# AIR_Connection.net
KiCad netlist of a schematic drawn in Altium Designer
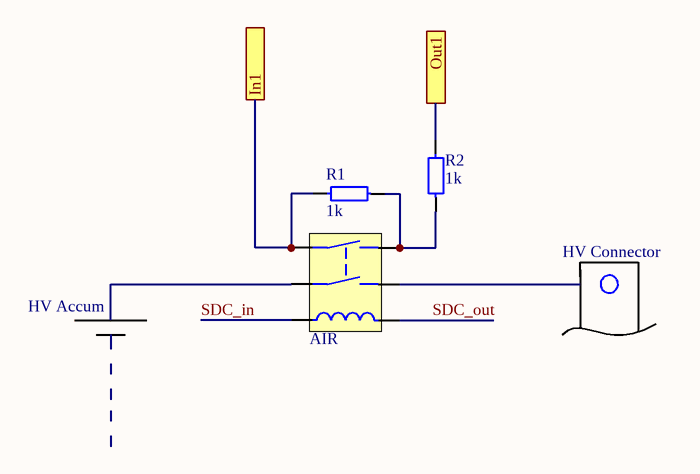
[diagram p0: AIR_Connection.SchDoc]

(export (version "E")
  (design (tool "Eeschema 10.0.6"))
  (components
    (comp (ref "*") (value "AIR") (libsource (lib "AIR") (part "Component_1")))
    (comp (ref "R1")
      (value "1k")
      (footprint "0603 Resistor")
      (description "0.1W 0603 12k, 1%")
      (fields (field (name "PART NUMBER") "RC0603FR-0712KL") (field (name "MANUFACTURER") "Taiwan"))
      (libsource (lib "BRT_Components") (part "Res 12k (0603)"))
    )
    (comp (ref "R2")
      (value "1k")
      (footprint "0603 Resistor")
      (description "0.1W 0603 12k, 1%")
      (fields (field (name "PART NUMBER") "RC0603FR-0712KL") (field (name "MANUFACTURER") "Taiwan"))
      (libsource (lib "BRT_Components") (part "Res 12k (0603)"))
    )
  )
  (nets
    (net (code "1") (name "/In1") (class "Default")
      (node (ref "*") (pin "4") (pinfunction "4_4") (pintype "passive"))
      (node (ref "R1") (pin "2") (pinfunction "2_2") (pintype "passive"))
    )
    (net (code "2") (name "/Out1") (class "Default")
      (node (ref "R2") (pin "2") (pinfunction "2_2") (pintype "passive"))
    )
    (net (code "3") (name "/SDC_in") (class "Default")
      (node (ref "*") (pin "1") (pinfunction "1_1") (pintype "passive"))
    )
    (net (code "4") (name "/SDC_out") (class "Default")
      (node (ref "*") (pin "2") (pinfunction "2_2") (pintype "passive"))
    )
    (net (code "5") (name "Net-(*-Pad3)") (class "Default")
      (node (ref "*") (pin "3") (pinfunction "3_3") (pintype "passive"))
      (node (ref "R1") (pin "1") (pinfunction "1_1") (pintype "passive"))
      (node (ref "R2") (pin "1") (pinfunction "1_1") (pintype "passive"))
    )
    (net (code "6") (name "unconnected-(*-Pad3)_1") (class "Default")
      (node (ref "*") (pin "3") (pinfunction "3_3") (pintype "passive"))
    )
    (net (code "7") (name "unconnected-(*-Pad4)") (class "Default")
      (node (ref "*") (pin "4") (pinfunction "4_4") (pintype "passive"))
    )
  )
)
